# SpO_Sensor.net
KiCad netlist of a schematic drawn in Altium Designer
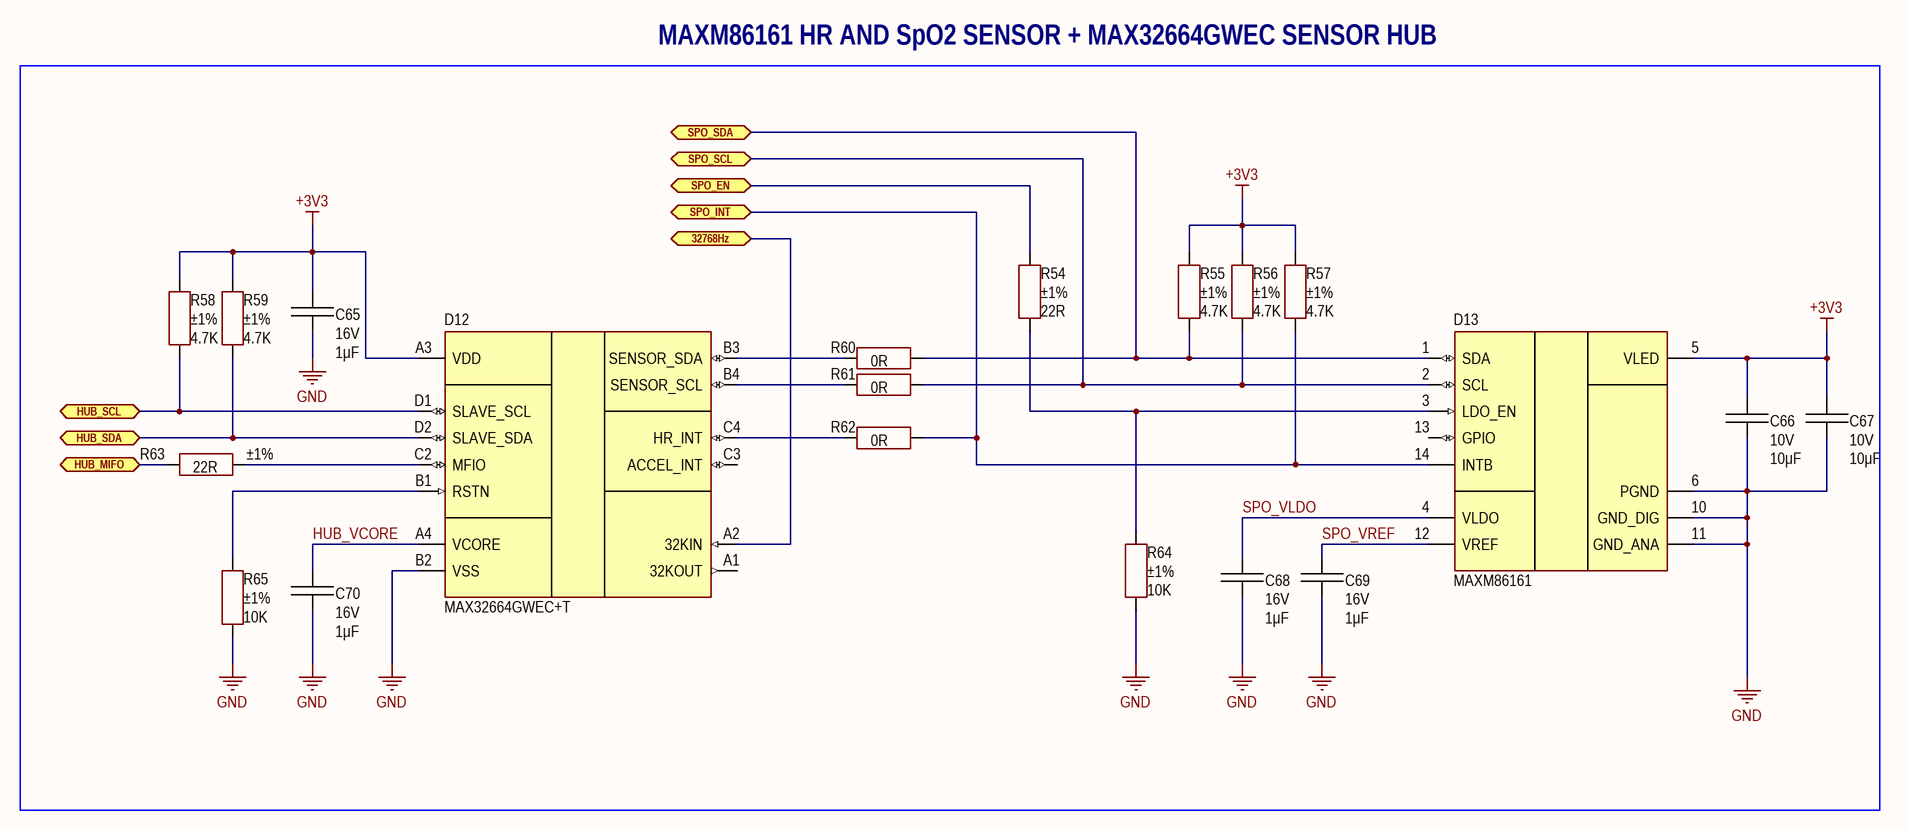
[diagram p0: SpO_Sensor — копия.SchDoc]

(export (version "E")
  (design (tool "Eeschema 10.0.6"))
  (components
    (comp (ref "C65")
      (value "1μF")
      (footprint "CAP: 0805")
      (description "1 µF ±10% 16V Ceramic Capacitor X7R 0805 (2012 Metric)")
      (fields
        (field (name "MANUFACTURER") "Yageo")
        (field (name "PARTNUMBER") "CC0805KKX7R7BB105")
        (field (name "VOLTAGE") "16V")
      )
      (libsource (lib "capacitor") (part "Ceramic_0805"))
    )
    (comp (ref "C66")
      (value "10μF")
      (footprint "CAP: 0805")
      (description "10 µF ±10% 10V Ceramic Capacitor X7R 0805 (2012 Metric)")
      (fields
        (field (name "MANUFACTURER") "Yageo")
        (field (name "PARTNUMBER") "CC0805KFX7R6BB106")
        (field (name "VOLTAGE") "10V")
      )
      (libsource (lib "capacitor") (part "Ceramic_0805"))
    )
    (comp (ref "C67")
      (value "10μF")
      (footprint "CAP: 0805")
      (description "10 µF ±10% 10V Ceramic Capacitor X7R 0805 (2012 Metric)")
      (fields
        (field (name "MANUFACTURER") "Yageo")
        (field (name "PARTNUMBER") "CC0805KFX7R6BB106")
        (field (name "VOLTAGE") "10V")
      )
      (libsource (lib "capacitor") (part "Ceramic_0805"))
    )
    (comp (ref "C68")
      (value "1μF")
      (footprint "CAP: 0805")
      (description "1 µF ±10% 16V Ceramic Capacitor X7R 0805 (2012 Metric)")
      (fields
        (field (name "MANUFACTURER") "Yageo")
        (field (name "PARTNUMBER") "CC0805KKX7R7BB105")
        (field (name "VOLTAGE") "16V")
      )
      (libsource (lib "capacitor") (part "Ceramic_0805"))
    )
    (comp (ref "C69")
      (value "1μF")
      (footprint "CAP: 0805")
      (description "1 µF ±10% 16V Ceramic Capacitor X7R 0805 (2012 Metric)")
      (fields
        (field (name "MANUFACTURER") "Yageo")
        (field (name "PARTNUMBER") "CC0805KKX7R7BB105")
        (field (name "VOLTAGE") "16V")
      )
      (libsource (lib "capacitor") (part "Ceramic_0805"))
    )
    (comp (ref "C70")
      (value "1μF")
      (footprint "CAP: 0805")
      (description "1 µF ±10% 16V Ceramic Capacitor X7R 0805 (2012 Metric)")
      (fields
        (field (name "MANUFACTURER") "Yageo")
        (field (name "PARTNUMBER") "CC0805KKX7R7BB105")
        (field (name "VOLTAGE") "16V")
      )
      (libsource (lib "capacitor") (part "Ceramic_0805"))
    )
    (comp (ref "D12")
      (value "~")
      (footprint "IC: 16-WLP")
      (description "Sensor Hub")
      (fields
        (field (name "MANUFACTURER") "Maxim Integrated")
        (field (name "VALUEMANUFACTURERPARTNUMBER") "IC Sensor Hub, Sensor Hub, , , , -40°C..+105°C, 16-WFL")
        (field (name "PARTNUMBER") "MAX32664GWEC+T")
      )
      (libsource (lib "MyLib") (part "MAX32664GWEC+T"))
    )
    (comp (ref "D13")
      (value "~")
      (footprint "IC: 14-OLGA")
      (description "HR and SpO2 sensor")
      (fields
        (field (name "MANUFACTURER") "Maxim Integrated")
        (field (name "VALUEMANUFACTURERPARTNUMBER") "IC HR and SpO2 sensor, HR and SpO2 sensor, , , , -40°C..+85°C, 14-OLGA")
        (field (name "PARTNUMBER") "MAXM86161")
      )
      (libsource (lib "MyLib") (part "MAXM86161"))
    )
    (comp (ref "R54")
      (value "22R")
      (footprint "RES: 0805")
      (description "22 Ohms ±1% 0.125W, 1/8W Chip Resistor 0805 (2012 Metric) Moisture Resistant Thick Film")
      (fields
        (field (name "MANUFACTURER") "Yageo")
        (field (name "PARTNUMBER") "RC0805FR-0722RL")
        (field (name "TOLERANCE") "±1%")
      )
      (libsource (lib "") (part "Resistor_0805_3"))
    )
    (comp (ref "R55")
      (value "4.7K")
      (footprint "RES: 0805")
      (description "4.7 kOhms ±5% 0.125W, 1/8W Chip Resistor 0805 (2012 Metric) Moisture Resistant Thick Film")
      (fields
        (field (name "MANUFACTURER") "Yageo")
        (field (name "PARTNUMBER") "RC0805JR-074K7L")
        (field (name "TOLERANCE") "±1%")
      )
      (libsource (lib "resistor") (part "Resistor_0805"))
    )
    (comp (ref "R56")
      (value "4.7K")
      (footprint "RES: 0805")
      (description "4.7 kOhms ±5% 0.125W, 1/8W Chip Resistor 0805 (2012 Metric) Moisture Resistant Thick Film")
      (fields
        (field (name "MANUFACTURER") "Yageo")
        (field (name "PARTNUMBER") "RC0805JR-074K7L")
        (field (name "TOLERANCE") "±1%")
      )
      (libsource (lib "resistor") (part "Resistor_0805"))
    )
    (comp (ref "R57")
      (value "4.7K")
      (footprint "RES: 0805")
      (description "4.7 kOhms ±5% 0.125W, 1/8W Chip Resistor 0805 (2012 Metric) Moisture Resistant Thick Film")
      (fields
        (field (name "MANUFACTURER") "Yageo")
        (field (name "PARTNUMBER") "RC0805JR-074K7L")
        (field (name "TOLERANCE") "±1%")
      )
      (libsource (lib "resistor") (part "Resistor_0805"))
    )
    (comp (ref "R58")
      (value "4.7K")
      (footprint "RES: 0805")
      (description "4.7 kOhms ±5% 0.125W, 1/8W Chip Resistor 0805 (2012 Metric) Moisture Resistant Thick Film")
      (fields
        (field (name "MANUFACTURER") "Yageo")
        (field (name "PARTNUMBER") "RC0805JR-074K7L")
        (field (name "TOLERANCE") "±1%")
      )
      (libsource (lib "resistor") (part "Resistor_0805"))
    )
    (comp (ref "R59")
      (value "4.7K")
      (footprint "RES: 0805")
      (description "4.7 kOhms ±5% 0.125W, 1/8W Chip Resistor 0805 (2012 Metric) Moisture Resistant Thick Film")
      (fields
        (field (name "MANUFACTURER") "Yageo")
        (field (name "PARTNUMBER") "RC0805JR-074K7L")
        (field (name "TOLERANCE") "±1%")
      )
      (libsource (lib "resistor") (part "Resistor_0805"))
    )
    (comp (ref "R60")
      (value "0R")
      (footprint "RES: 0805")
      (description "0 Ohms Jumper 0.125W, 1/8W Chip Resistor 0805 (2012 Metric) Moisture Resistant Thick Film")
      (fields (field (name "MANUFACTURER") "Yageo") (field (name "PARTNUMBER") "RC0805JR-070RL"))
      (libsource (lib "") (part "Resistor_0805_1"))
    )
    (comp (ref "R61")
      (value "0R")
      (footprint "RES: 0805")
      (description "0 Ohms Jumper 0.125W, 1/8W Chip Resistor 0805 (2012 Metric) Moisture Resistant Thick Film")
      (fields (field (name "MANUFACTURER") "Yageo") (field (name "PARTNUMBER") "RC0805JR-070RL"))
      (libsource (lib "") (part "Resistor_0805_1"))
    )
    (comp (ref "R62")
      (value "0R")
      (footprint "RES: 0805")
      (description "0 Ohms Jumper 0.125W, 1/8W Chip Resistor 0805 (2012 Metric) Moisture Resistant Thick Film")
      (fields (field (name "MANUFACTURER") "Yageo") (field (name "PARTNUMBER") "RC0805JR-070RL"))
      (libsource (lib "") (part "Resistor_0805_1"))
    )
    (comp (ref "R63")
      (value "22R")
      (footprint "RES: 0805")
      (description "22 Ohms ±1% 0.125W, 1/8W Chip Resistor 0805 (2012 Metric) Moisture Resistant Thick Film")
      (fields
        (field (name "MANUFACTURER") "Yageo")
        (field (name "PARTNUMBER") "RC0805FR-0722RL")
        (field (name "TOLERANCE") "±1%")
      )
      (libsource (lib "") (part "Resistor_0805_2"))
    )
    (comp (ref "R64")
      (value "10K")
      (footprint "RES: 0805")
      (description "10 kOhms ±1% 0.125W, 1/8W Chip Resistor 0805 (2012 Metric) Moisture Resistant Thick Film")
      (fields
        (field (name "MANUFACTURER") "Yageo")
        (field (name "PARTNUMBER") "RC0805FR-0710KL")
        (field (name "TOLERANCE") "±1%")
      )
      (libsource (lib "resistor") (part "Resistor_0805"))
    )
    (comp (ref "R65")
      (value "10K")
      (footprint "RES: 0805")
      (description "10 kOhms ±1% 0.125W, 1/8W Chip Resistor 0805 (2012 Metric) Moisture Resistant Thick Film")
      (fields
        (field (name "MANUFACTURER") "Yageo")
        (field (name "PARTNUMBER") "RC0805FR-0710KL")
        (field (name "TOLERANCE") "±1%")
      )
      (libsource (lib "resistor") (part "Resistor_0805"))
    )
  )
  (nets
    (net (code "1") (name "+3V3") (class "Default")
      (node (ref "C65") (pin "2") (pinfunction "2_2") (pintype "passive"))
      (node (ref "C66") (pin "2") (pinfunction "2_2") (pintype "passive"))
      (node (ref "C67") (pin "2") (pinfunction "2_2") (pintype "passive"))
      (node (ref "D12") (pin "A3") (pinfunction "VDD_A3") (pintype "power_in"))
      (node (ref "D13") (pin "5") (pinfunction "VLED_5") (pintype "power_in"))
      (node (ref "R55") (pin "1") (pinfunction "1_1") (pintype "passive"))
      (node (ref "R56") (pin "1") (pinfunction "1_1") (pintype "passive"))
      (node (ref "R57") (pin "1") (pinfunction "1_1") (pintype "passive"))
      (node (ref "R58") (pin "1") (pinfunction "1_1") (pintype "passive"))
      (node (ref "R59") (pin "1") (pinfunction "1_1") (pintype "passive"))
    )
    (net (code "2") (name "/32768Hz") (class "Default")
      (node (ref "D12") (pin "A2") (pinfunction "32KIN_A2") (pintype "input"))
    )
    (net (code "3") (name "/HUB_MIFO") (class "Default")
      (node (ref "R63") (pin "1") (pinfunction "1_1") (pintype "passive"))
    )
    (net (code "4") (name "/HUB_SCL") (class "Default")
      (node (ref "D12") (pin "D1") (pinfunction "SLAVE_SCL_D1") (pintype "bidirectional"))
      (node (ref "R58") (pin "2") (pinfunction "2_2") (pintype "passive"))
    )
    (net (code "5") (name "/HUB_SDA") (class "Default")
      (node (ref "D12") (pin "D2") (pinfunction "SLAVE_SDA_D2") (pintype "bidirectional"))
      (node (ref "R59") (pin "2") (pinfunction "2_2") (pintype "passive"))
    )
    (net (code "6") (name "/HUB_VCORE") (class "Default")
      (node (ref "C70") (pin "2") (pinfunction "2_2") (pintype "passive"))
      (node (ref "D12") (pin "A4") (pinfunction "VCORE_A4") (pintype "power_in"))
    )
    (net (code "7") (name "/SPO_EN") (class "Default")
      (node (ref "R54") (pin "2") (pinfunction "2_2") (pintype "passive"))
    )
    (net (code "8") (name "/SPO_INT") (class "Default")
      (node (ref "D13") (pin "14") (pinfunction "INTB_14") (pintype "open_collector"))
      (node (ref "R57") (pin "2") (pinfunction "2_2") (pintype "passive"))
      (node (ref "R62") (pin "1") (pinfunction "1_1") (pintype "passive"))
    )
    (net (code "9") (name "/SPO_SCL") (class "Default")
      (node (ref "D13") (pin "2") (pinfunction "SCL_2") (pintype "bidirectional"))
      (node (ref "R56") (pin "2") (pinfunction "2_2") (pintype "passive"))
      (node (ref "R61") (pin "1") (pinfunction "1_1") (pintype "passive"))
    )
    (net (code "10") (name "/SPO_SDA") (class "Default")
      (node (ref "D13") (pin "1") (pinfunction "SDA_1") (pintype "bidirectional"))
      (node (ref "R55") (pin "2") (pinfunction "2_2") (pintype "passive"))
      (node (ref "R60") (pin "1") (pinfunction "1_1") (pintype "passive"))
    )
    (net (code "11") (name "/SPO_VLDO") (class "Default")
      (node (ref "C68") (pin "2") (pinfunction "2_2") (pintype "passive"))
      (node (ref "D13") (pin "4") (pinfunction "VLDO_4") (pintype "power_in"))
    )
    (net (code "12") (name "/SPO_VREF") (class "Default")
      (node (ref "C69") (pin "2") (pinfunction "2_2") (pintype "passive"))
      (node (ref "D13") (pin "12") (pinfunction "VREF_12") (pintype "power_in"))
    )
    (net (code "13") (name "GND") (class "Default")
      (node (ref "C65") (pin "1") (pinfunction "1_1") (pintype "passive"))
      (node (ref "C66") (pin "1") (pinfunction "1_1") (pintype "passive"))
      (node (ref "C67") (pin "1") (pinfunction "1_1") (pintype "passive"))
      (node (ref "C68") (pin "1") (pinfunction "1_1") (pintype "passive"))
      (node (ref "C69") (pin "1") (pinfunction "1_1") (pintype "passive"))
      (node (ref "C70") (pin "1") (pinfunction "1_1") (pintype "passive"))
      (node (ref "D12") (pin "B2") (pinfunction "VSS_B2") (pintype "power_in"))
      (node (ref "D13") (pin "10") (pinfunction "GND_DIG_10") (pintype "power_in"))
      (node (ref "D13") (pin "11") (pinfunction "GND_ANA_11") (pintype "power_in"))
      (node (ref "D13") (pin "6") (pinfunction "PGND_6") (pintype "power_in"))
      (node (ref "R64") (pin "2") (pinfunction "2_2") (pintype "passive"))
      (node (ref "R65") (pin "2") (pinfunction "2_2") (pintype "passive"))
    )
    (net (code "14") (name "Net-(D12-HR_INT)") (class "Default")
      (node (ref "D12") (pin "C4") (pinfunction "HR_INT_C4") (pintype "bidirectional"))
      (node (ref "R62") (pin "2") (pinfunction "2_2") (pintype "passive"))
    )
    (net (code "15") (name "Net-(D12-MFIO)") (class "Default")
      (node (ref "D12") (pin "C2") (pinfunction "MFIO_C2") (pintype "bidirectional"))
      (node (ref "R63") (pin "2") (pinfunction "2_2") (pintype "passive"))
    )
    (net (code "16") (name "Net-(D12-RSTN)") (class "Default")
      (node (ref "D12") (pin "B1") (pinfunction "RSTN_B1") (pintype "input"))
      (node (ref "R65") (pin "1") (pinfunction "1_1") (pintype "passive"))
    )
    (net (code "17") (name "Net-(D12-SENSOR_SCL)") (class "Default")
      (node (ref "D12") (pin "B4") (pinfunction "SENSOR_SCL_B4") (pintype "bidirectional"))
      (node (ref "R61") (pin "2") (pinfunction "2_2") (pintype "passive"))
    )
    (net (code "18") (name "Net-(D12-SENSOR_SDA)") (class "Default")
      (node (ref "D12") (pin "B3") (pinfunction "SENSOR_SDA_B3") (pintype "bidirectional"))
      (node (ref "R60") (pin "2") (pinfunction "2_2") (pintype "passive"))
    )
    (net (code "19") (name "Net-(D13-LDO_EN)") (class "Default")
      (node (ref "D13") (pin "3") (pinfunction "LDO_EN_3") (pintype "input"))
      (node (ref "R54") (pin "1") (pinfunction "1_1") (pintype "passive"))
      (node (ref "R64") (pin "1") (pinfunction "1_1") (pintype "passive"))
    )
    (net (code "20") (name "unconnected-(D12-32KOUT-PadA1)") (class "Default")
      (node (ref "D12") (pin "A1") (pinfunction "32KOUT_A1") (pintype "output"))
    )
    (net (code "21") (name "unconnected-(D12-ACCEL_INT-PadC3)") (class "Default")
      (node (ref "D12") (pin "C3") (pinfunction "ACCEL_INT_C3") (pintype "bidirectional"))
    )
    (net (code "22") (name "unconnected-(D13-GPIO-Pad13)") (class "Default")
      (node (ref "D13") (pin "13") (pinfunction "GPIO_13") (pintype "bidirectional"))
    )
  )
)
